# Smart_home.net
KiCad netlist of a schematic drawn in Altium Designer
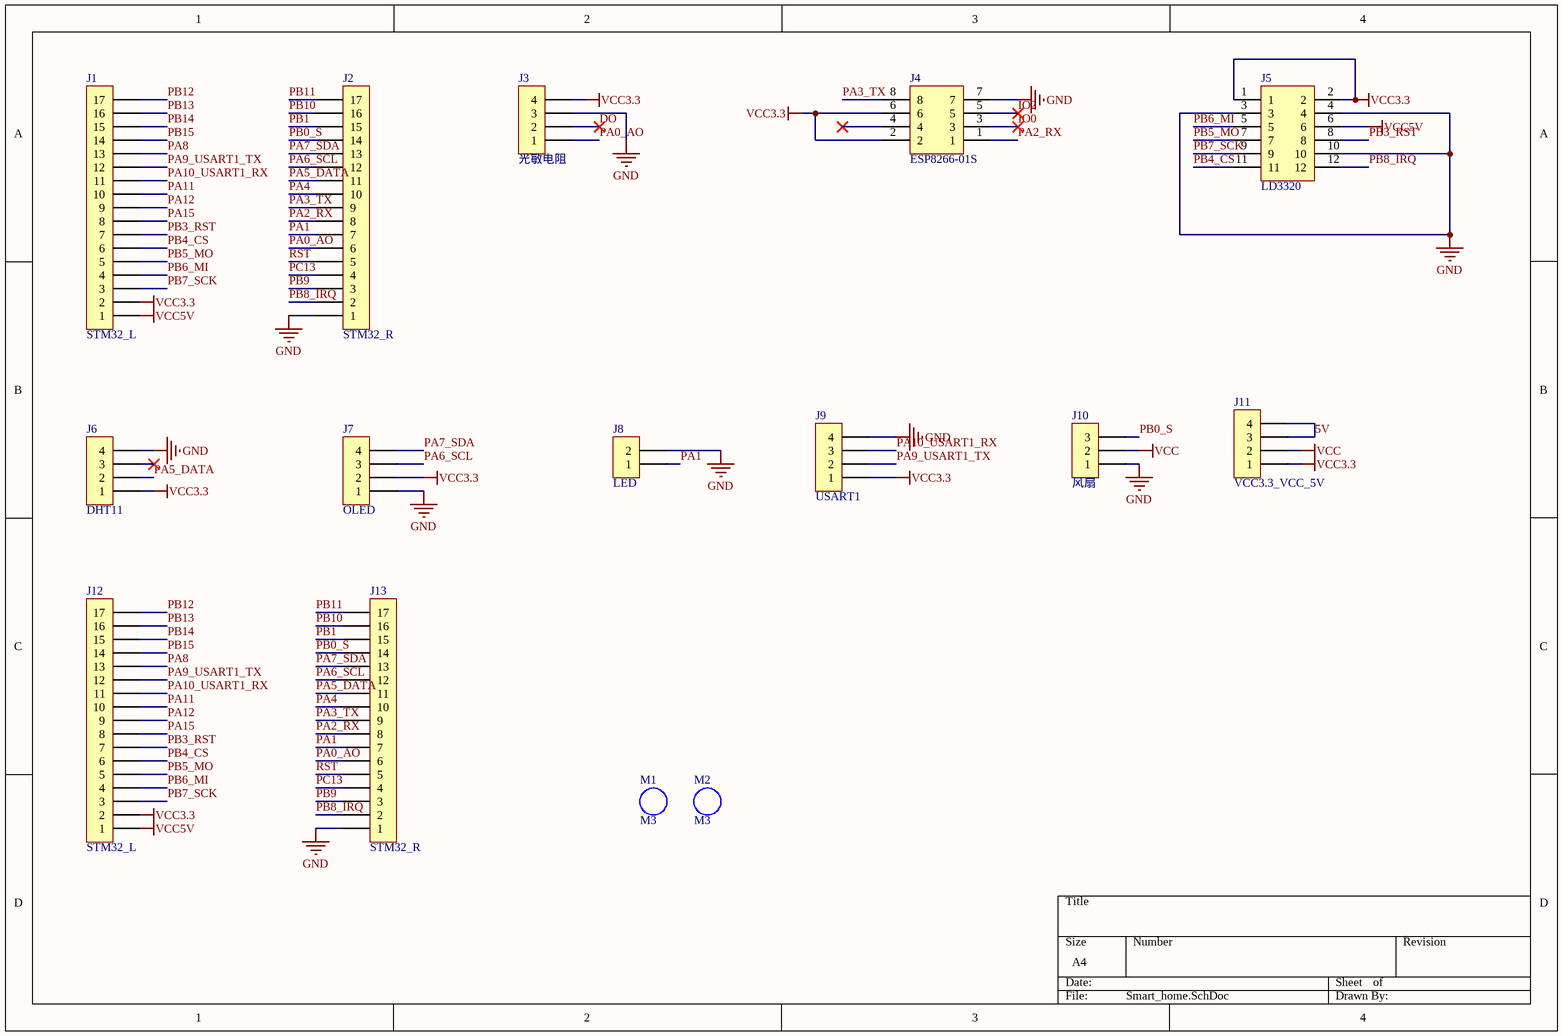
[diagram p0: Smart_home.SchDoc]

(export (version "E")
  (design (tool "Eeschema 10.0.6"))
  (components
    (comp (ref "J1")
      (value "STM32_L")
      (footprint "Fe-HDR1X17/2.54-S")
      (libsource (lib "") (part "Female HDR1X17_1"))
    )
    (comp (ref "J2")
      (value "STM32_R")
      (footprint "Fe-HDR1X17/2.54-S")
      (libsource (lib "Smart_home") (part "Female HDR1X17"))
    )
    (comp (ref "J3")
      (value "光敏电阻")
      (footprint "Fe-HDR1X4/2.54-S")
      (libsource (lib "Smart_home") (part "Female HDR1X4"))
    )
    (comp (ref "J4")
      (value "ESP8266-01S")
      (footprint "Fe-HDR2X4/2.54-S")
      (libsource (lib "Smart_home") (part "Female HDR2X4"))
    )
    (comp (ref "J5")
      (value "LD3320")
      (footprint "Fe-HDR2X6/2.54-S")
      (libsource (lib "Smart_home") (part "Female HDR2X6"))
    )
    (comp (ref "J6")
      (value "DHT11")
      (footprint "Fe-HDR1X4/2.54-S")
      (libsource (lib "Smart_home") (part "Female HDR1X4"))
    )
    (comp (ref "J7")
      (value "OLED")
      (footprint "Fe-HDR1X4/2.54-S")
      (libsource (lib "Smart_home") (part "Female HDR1X4"))
    )
    (comp (ref "J8")
      (value "LED")
      (footprint "Fe-HDR1X2/2.54-S")
      (libsource (lib "Smart_home") (part "Female HDR1X2"))
    )
    (comp (ref "J9")
      (value "USART1")
      (footprint "Fe-HDR1X4/2.54-S")
      (libsource (lib "Smart_home") (part "Female HDR1X4"))
    )
    (comp (ref "J10")
      (value "风扇")
      (footprint "Pin HDR1X3/2.54mm-S")
      (libsource (lib "Smart_home") (part "Pin HDR1X3"))
    )
    (comp (ref "J11")
      (value "VCC3.3_VCC_5V")
      (footprint "Pin HDR1X4/2.54mm-S")
      (libsource (lib "Smart_home") (part "Pin HDR1X4"))
    )
    (comp (ref "J12")
      (value "STM32_L")
      (footprint "Fe-HDR1X17/2.54-S")
      (libsource (lib "") (part "Female HDR1X17_1"))
    )
    (comp (ref "J13")
      (value "STM32_R")
      (footprint "Fe-HDR1X17/2.54-S")
      (libsource (lib "Smart_home") (part "Female HDR1X17"))
    )
    (comp (ref "M1")
      (value "M3")
      (footprint "M3 125X300")
      (description "铜柱孔")
      (fields (field (name "版权归属") "源创客"))
      (libsource (lib "Smart_home") (part "M3"))
    )
    (comp (ref "M2")
      (value "M3")
      (footprint "M3 125X300")
      (description "铜柱孔")
      (fields (field (name "版权归属") "源创客"))
      (libsource (lib "Smart_home") (part "M3"))
    )
  )
  (nets
    (net (code "1") (name "/5V") (class "Default")
      (node (ref "J11") (pin "3") (pinfunction "3_3") (pintype "passive"))
      (node (ref "J11") (pin "4") (pinfunction "4_4") (pintype "passive"))
    )
    (net (code "2") (name "/DO") (class "Default")
      (node (ref "J3") (pin "2") (pinfunction "2_2") (pintype "passive+no_connect"))
    )
    (net (code "3") (name "/IO0") (class "Default")
      (node (ref "J4") (pin "3") (pinfunction "3_3") (pintype "passive+no_connect"))
    )
    (net (code "4") (name "/IO2") (class "Default")
      (node (ref "J4") (pin "5") (pinfunction "5_5") (pintype "passive+no_connect"))
    )
    (net (code "5") (name "/PA0_AO") (class "Default")
      (node (ref "J13") (pin "6") (pinfunction "6_6") (pintype "passive"))
      (node (ref "J2") (pin "6") (pinfunction "6_6") (pintype "passive"))
      (node (ref "J3") (pin "1") (pinfunction "1_1") (pintype "passive"))
    )
    (net (code "6") (name "/PA1") (class "Default")
      (node (ref "J13") (pin "7") (pinfunction "7_7") (pintype "passive"))
      (node (ref "J2") (pin "7") (pinfunction "7_7") (pintype "passive"))
      (node (ref "J8") (pin "1") (pinfunction "1_1") (pintype "passive"))
    )
    (net (code "7") (name "/PA2_RX") (class "Default")
      (node (ref "J13") (pin "8") (pinfunction "8_8") (pintype "passive"))
      (node (ref "J2") (pin "8") (pinfunction "8_8") (pintype "passive"))
      (node (ref "J4") (pin "1") (pinfunction "1_1") (pintype "passive"))
    )
    (net (code "8") (name "/PA3_TX") (class "Default")
      (node (ref "J13") (pin "9") (pinfunction "9_9") (pintype "passive"))
      (node (ref "J2") (pin "9") (pinfunction "9_9") (pintype "passive"))
      (node (ref "J4") (pin "8") (pinfunction "8_8") (pintype "passive"))
    )
    (net (code "9") (name "/PA4") (class "Default")
      (node (ref "J13") (pin "10") (pinfunction "10_10") (pintype "passive"))
      (node (ref "J2") (pin "10") (pinfunction "10_10") (pintype "passive"))
    )
    (net (code "10") (name "/PA5_DATA") (class "Default")
      (node (ref "J13") (pin "11") (pinfunction "11_11") (pintype "passive"))
      (node (ref "J2") (pin "11") (pinfunction "11_11") (pintype "passive"))
      (node (ref "J6") (pin "2") (pinfunction "2_2") (pintype "passive"))
    )
    (net (code "11") (name "/PA6_SCL") (class "Default")
      (node (ref "J13") (pin "12") (pinfunction "12_12") (pintype "passive"))
      (node (ref "J2") (pin "12") (pinfunction "12_12") (pintype "passive"))
      (node (ref "J7") (pin "3") (pinfunction "3_3") (pintype "passive"))
    )
    (net (code "12") (name "/PA7_SDA") (class "Default")
      (node (ref "J13") (pin "13") (pinfunction "13_13") (pintype "passive"))
      (node (ref "J2") (pin "13") (pinfunction "13_13") (pintype "passive"))
      (node (ref "J7") (pin "4") (pinfunction "4_4") (pintype "passive"))
    )
    (net (code "13") (name "/PA8") (class "Default")
      (node (ref "J1") (pin "13") (pinfunction "13_13") (pintype "passive"))
      (node (ref "J12") (pin "13") (pinfunction "13_13") (pintype "passive"))
    )
    (net (code "14") (name "/PA9_USART1_TX") (class "Default")
      (node (ref "J1") (pin "12") (pinfunction "12_12") (pintype "passive"))
      (node (ref "J12") (pin "12") (pinfunction "12_12") (pintype "passive"))
      (node (ref "J9") (pin "2") (pinfunction "2_2") (pintype "passive"))
    )
    (net (code "15") (name "/PA10_USART1_RX") (class "Default")
      (node (ref "J1") (pin "11") (pinfunction "11_11") (pintype "passive"))
      (node (ref "J12") (pin "11") (pinfunction "11_11") (pintype "passive"))
      (node (ref "J9") (pin "3") (pinfunction "3_3") (pintype "passive"))
    )
    (net (code "16") (name "/PA11") (class "Default")
      (node (ref "J1") (pin "10") (pinfunction "10_10") (pintype "passive"))
      (node (ref "J12") (pin "10") (pinfunction "10_10") (pintype "passive"))
    )
    (net (code "17") (name "/PA12") (class "Default")
      (node (ref "J1") (pin "9") (pinfunction "9_9") (pintype "passive"))
      (node (ref "J12") (pin "9") (pinfunction "9_9") (pintype "passive"))
    )
    (net (code "18") (name "/PA15") (class "Default")
      (node (ref "J1") (pin "8") (pinfunction "8_8") (pintype "passive"))
      (node (ref "J12") (pin "8") (pinfunction "8_8") (pintype "passive"))
    )
    (net (code "19") (name "/PB0_S") (class "Default")
      (node (ref "J10") (pin "3") (pinfunction "3_3") (pintype "passive"))
      (node (ref "J13") (pin "14") (pinfunction "14_14") (pintype "passive"))
      (node (ref "J2") (pin "14") (pinfunction "14_14") (pintype "passive"))
    )
    (net (code "20") (name "/PB1") (class "Default")
      (node (ref "J13") (pin "15") (pinfunction "15_15") (pintype "passive"))
      (node (ref "J2") (pin "15") (pinfunction "15_15") (pintype "passive"))
    )
    (net (code "21") (name "/PB3_RST") (class "Default")
      (node (ref "J1") (pin "7") (pinfunction "7_7") (pintype "passive"))
      (node (ref "J12") (pin "7") (pinfunction "7_7") (pintype "passive"))
      (node (ref "J5") (pin "8") (pinfunction "8_8") (pintype "passive"))
    )
    (net (code "22") (name "/PB4_CS") (class "Default")
      (node (ref "J1") (pin "6") (pinfunction "6_6") (pintype "passive"))
      (node (ref "J12") (pin "6") (pinfunction "6_6") (pintype "passive"))
      (node (ref "J5") (pin "11") (pinfunction "11_11") (pintype "passive"))
    )
    (net (code "23") (name "/PB5_MO") (class "Default")
      (node (ref "J1") (pin "5") (pinfunction "5_5") (pintype "passive"))
      (node (ref "J12") (pin "5") (pinfunction "5_5") (pintype "passive"))
      (node (ref "J5") (pin "7") (pinfunction "7_7") (pintype "passive"))
    )
    (net (code "24") (name "/PB6_MI") (class "Default")
      (node (ref "J1") (pin "4") (pinfunction "4_4") (pintype "passive"))
      (node (ref "J12") (pin "4") (pinfunction "4_4") (pintype "passive"))
      (node (ref "J5") (pin "5") (pinfunction "5_5") (pintype "passive"))
    )
    (net (code "25") (name "/PB7_SCK") (class "Default")
      (node (ref "J1") (pin "3") (pinfunction "3_3") (pintype "passive"))
      (node (ref "J12") (pin "3") (pinfunction "3_3") (pintype "passive"))
      (node (ref "J5") (pin "9") (pinfunction "9_9") (pintype "passive"))
    )
    (net (code "26") (name "/PB8_IRQ") (class "Default")
      (node (ref "J13") (pin "2") (pinfunction "2_2") (pintype "passive"))
      (node (ref "J2") (pin "2") (pinfunction "2_2") (pintype "passive"))
      (node (ref "J5") (pin "12") (pinfunction "12_12") (pintype "passive"))
    )
    (net (code "27") (name "/PB9") (class "Default")
      (node (ref "J13") (pin "3") (pinfunction "3_3") (pintype "passive"))
      (node (ref "J2") (pin "3") (pinfunction "3_3") (pintype "passive"))
    )
    (net (code "28") (name "/PB10") (class "Default")
      (node (ref "J13") (pin "16") (pinfunction "16_16") (pintype "passive"))
      (node (ref "J2") (pin "16") (pinfunction "16_16") (pintype "passive"))
    )
    (net (code "29") (name "/PB11") (class "Default")
      (node (ref "J13") (pin "17") (pinfunction "17_17") (pintype "passive"))
      (node (ref "J2") (pin "17") (pinfunction "17_17") (pintype "passive"))
    )
    (net (code "30") (name "/PB12") (class "Default")
      (node (ref "J1") (pin "17") (pinfunction "17_17") (pintype "passive"))
      (node (ref "J12") (pin "17") (pinfunction "17_17") (pintype "passive"))
    )
    (net (code "31") (name "/PB13") (class "Default")
      (node (ref "J1") (pin "16") (pinfunction "16_16") (pintype "passive"))
      (node (ref "J12") (pin "16") (pinfunction "16_16") (pintype "passive"))
    )
    (net (code "32") (name "/PB14") (class "Default")
      (node (ref "J1") (pin "15") (pinfunction "15_15") (pintype "passive"))
      (node (ref "J12") (pin "15") (pinfunction "15_15") (pintype "passive"))
    )
    (net (code "33") (name "/PB15") (class "Default")
      (node (ref "J1") (pin "14") (pinfunction "14_14") (pintype "passive"))
      (node (ref "J12") (pin "14") (pinfunction "14_14") (pintype "passive"))
    )
    (net (code "34") (name "/PC13") (class "Default")
      (node (ref "J13") (pin "4") (pinfunction "4_4") (pintype "passive"))
      (node (ref "J2") (pin "4") (pinfunction "4_4") (pintype "passive"))
    )
    (net (code "35") (name "/RST") (class "Default")
      (node (ref "J13") (pin "5") (pinfunction "5_5") (pintype "passive"))
      (node (ref "J2") (pin "5") (pinfunction "5_5") (pintype "passive"))
    )
    (net (code "36") (name "GND") (class "Default")
      (node (ref "J10") (pin "1") (pinfunction "1_1") (pintype "passive"))
      (node (ref "J13") (pin "1") (pinfunction "1_1") (pintype "passive"))
      (node (ref "J2") (pin "1") (pinfunction "1_1") (pintype "passive"))
      (node (ref "J3") (pin "3") (pinfunction "3_3") (pintype "passive"))
      (node (ref "J4") (pin "7") (pinfunction "7_7") (pintype "passive"))
      (node (ref "J5") (pin "10") (pinfunction "10_10") (pintype "passive"))
      (node (ref "J5") (pin "3") (pinfunction "3_3") (pintype "passive"))
      (node (ref "J5") (pin "4") (pinfunction "4_4") (pintype "passive"))
      (node (ref "J6") (pin "4") (pinfunction "4_4") (pintype "passive"))
      (node (ref "J7") (pin "1") (pinfunction "1_1") (pintype "passive"))
      (node (ref "J8") (pin "2") (pinfunction "2_2") (pintype "passive"))
      (node (ref "J9") (pin "4") (pinfunction "4_4") (pintype "passive"))
    )
    (net (code "37") (name "VCC") (class "Default")
      (node (ref "J10") (pin "2") (pinfunction "2_2") (pintype "passive"))
      (node (ref "J11") (pin "2") (pinfunction "2_2") (pintype "passive"))
    )
    (net (code "38") (name "VCC3.3") (class "Default")
      (node (ref "J1") (pin "2") (pinfunction "2_2") (pintype "passive"))
      (node (ref "J11") (pin "1") (pinfunction "1_1") (pintype "passive"))
      (node (ref "J12") (pin "2") (pinfunction "2_2") (pintype "passive"))
      (node (ref "J3") (pin "4") (pinfunction "4_4") (pintype "passive"))
      (node (ref "J4") (pin "2") (pinfunction "2_2") (pintype "passive"))
      (node (ref "J4") (pin "6") (pinfunction "6_6") (pintype "passive"))
      (node (ref "J5") (pin "1") (pinfunction "1_1") (pintype "passive"))
      (node (ref "J5") (pin "2") (pinfunction "2_2") (pintype "passive"))
      (node (ref "J6") (pin "1") (pinfunction "1_1") (pintype "passive"))
      (node (ref "J7") (pin "2") (pinfunction "2_2") (pintype "passive"))
      (node (ref "J9") (pin "1") (pinfunction "1_1") (pintype "passive"))
    )
    (net (code "39") (name "VCC5V") (class "Default")
      (node (ref "J1") (pin "1") (pinfunction "1_1") (pintype "passive"))
      (node (ref "J12") (pin "1") (pinfunction "1_1") (pintype "passive"))
      (node (ref "J5") (pin "6") (pinfunction "6_6") (pintype "passive"))
    )
    (net (code "40") (name "unconnected-(J4-Pad4)") (class "Default")
      (node (ref "J4") (pin "4") (pinfunction "4_4") (pintype "passive+no_connect"))
    )
    (net (code "41") (name "unconnected-(J6-Pad3)") (class "Default")
      (node (ref "J6") (pin "3") (pinfunction "3_3") (pintype "passive+no_connect"))
    )
  )
)
